# OSSI-1_Beacon_3.net
KiCad netlist of a schematic drawn in Altium Designer
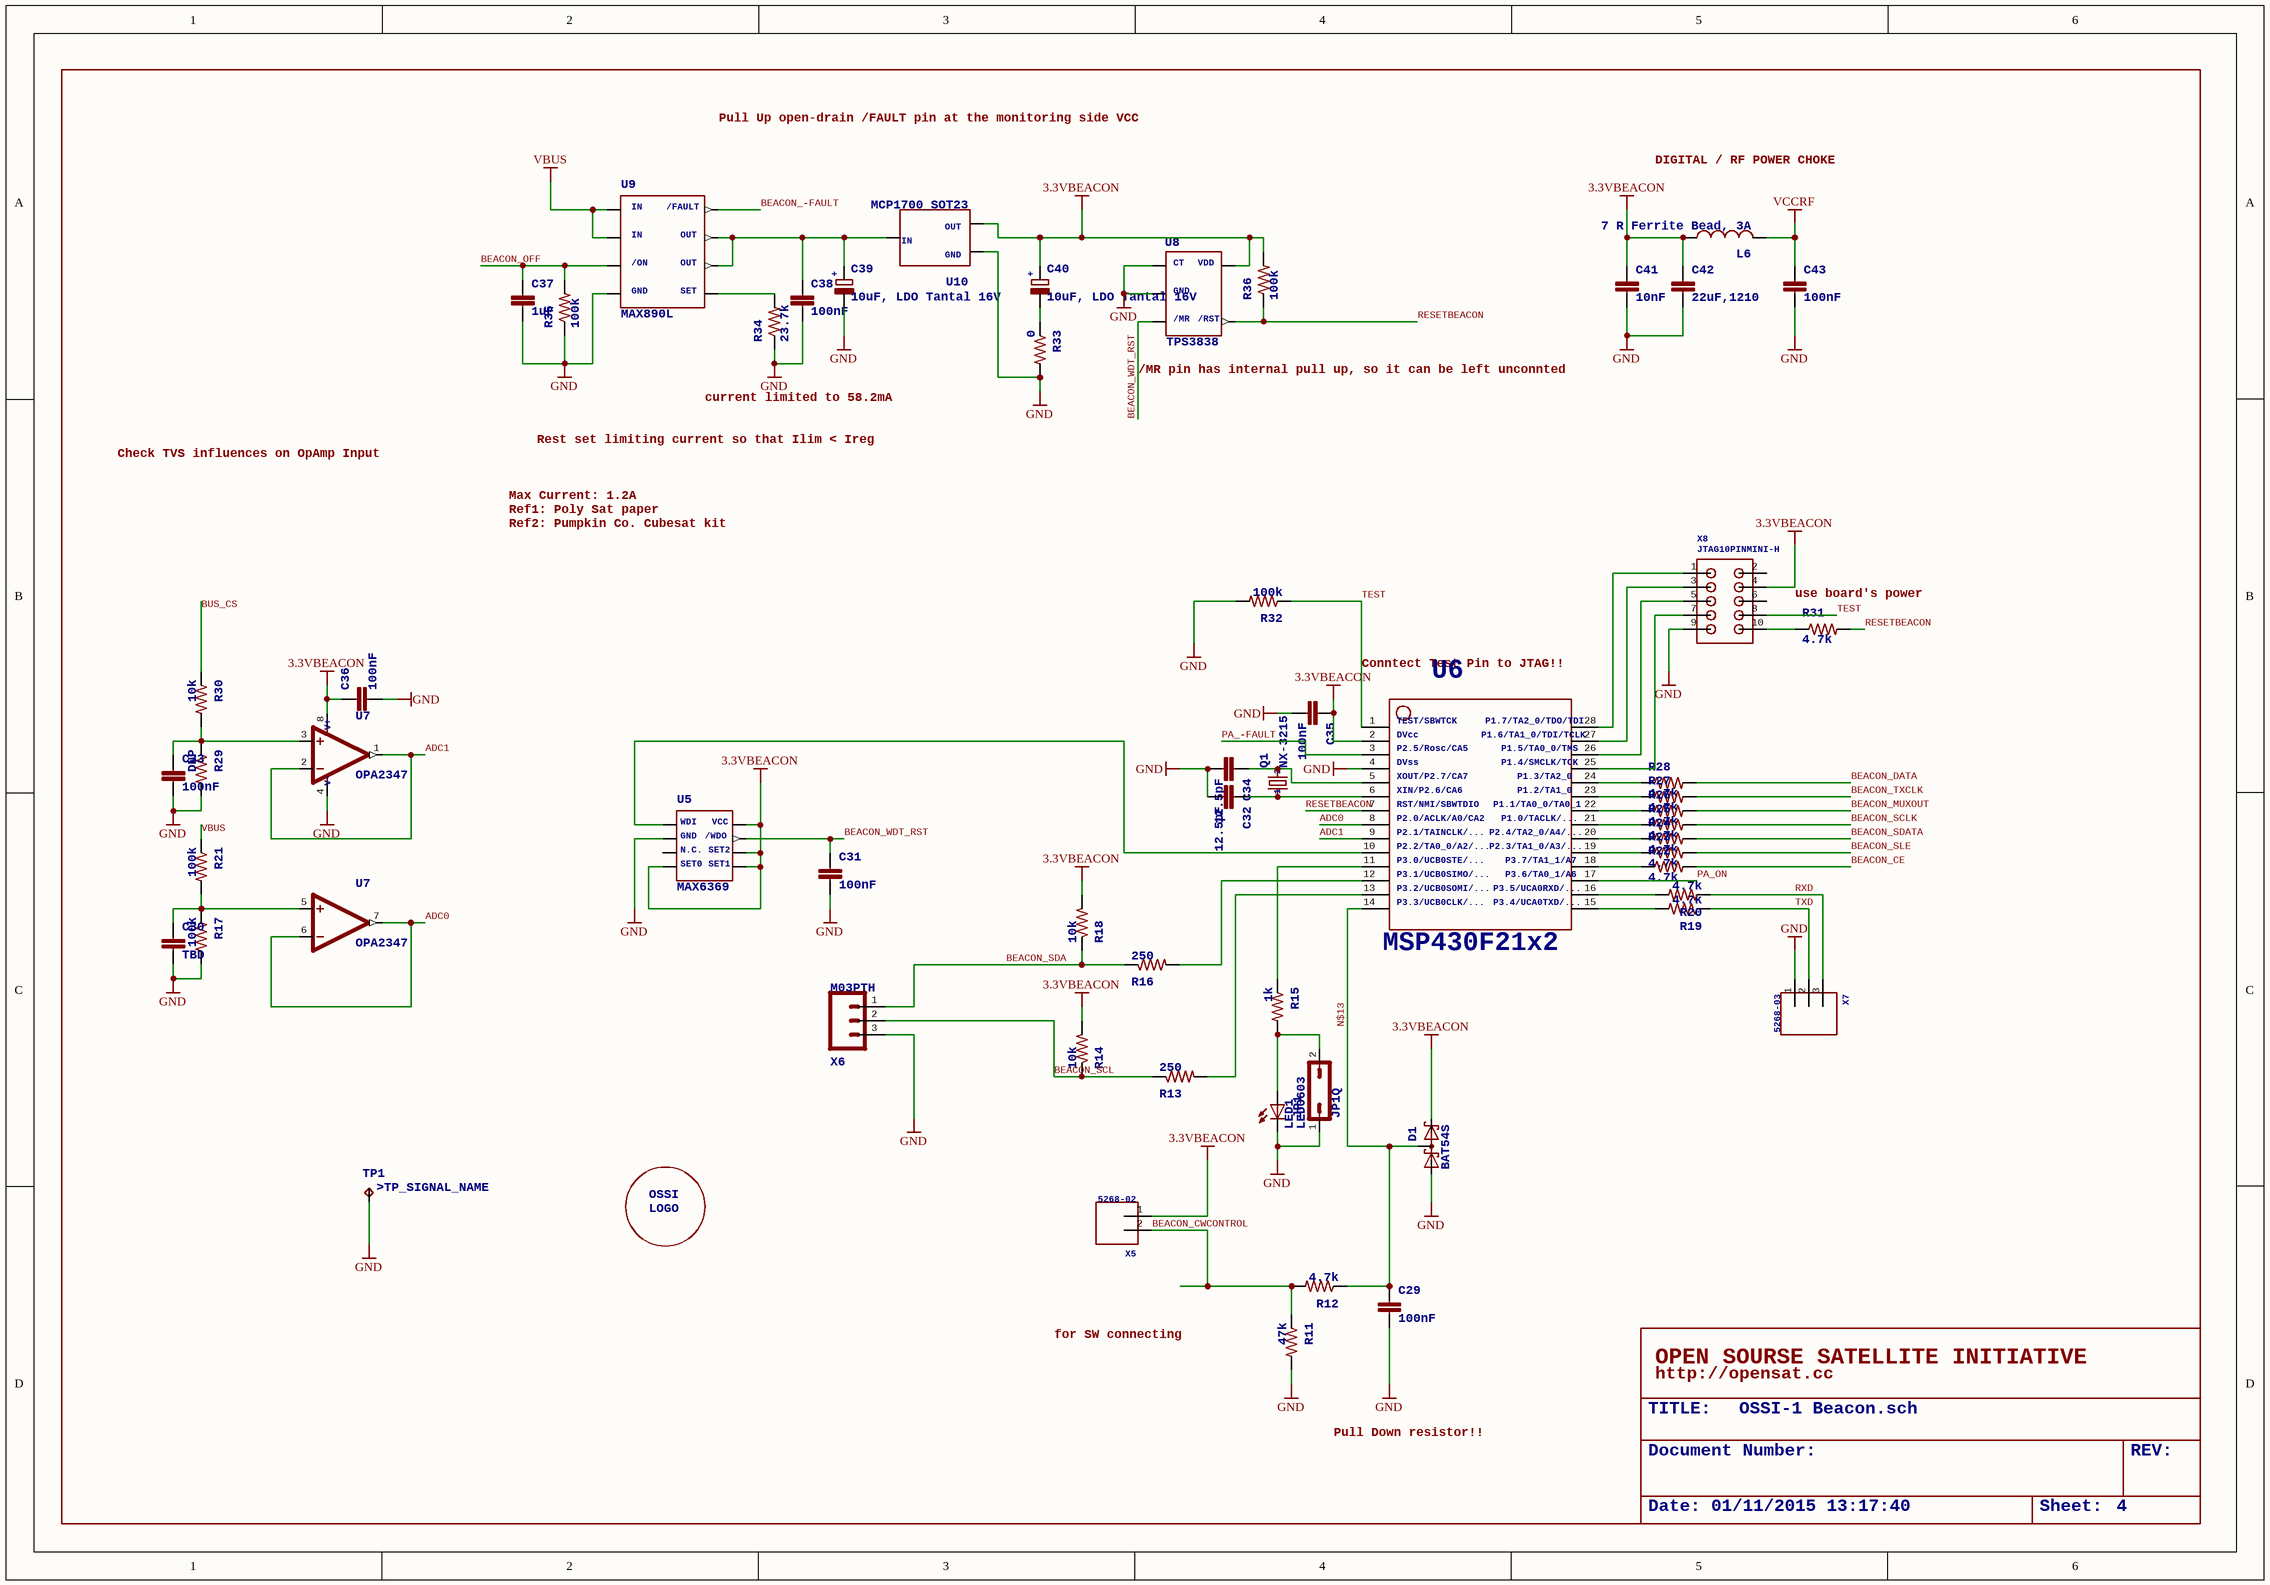
[diagram p0: OSSI-1 Beacon_3.SchDoc]

(export (version "E")
  (design (tool "Eeschema 10.0.6"))
  (components
    (comp (ref "C29")
      (value "100nF")
      (footprint "C0603(1608)")
      (fields (field (name ">NAME") "C29") (field (name ">VALUE") "100nF"))
      (libsource (lib "OSSI") (part "C0603(1608)"))
    )
    (comp (ref "C30")
      (value "TBD")
      (footprint "C0603(1608)")
      (fields (field (name ">NAME") "C30") (field (name ">VALUE") "TBD"))
      (libsource (lib "OSSI") (part "C0603(1608)"))
    )
    (comp (ref "C31")
      (value "100nF")
      (footprint "C0603(1608)")
      (fields (field (name ">NAME") "C31") (field (name ">VALUE") "100nF"))
      (libsource (lib "OSSI") (part "C0603(1608)"))
    )
    (comp (ref "C32")
      (value "12.5pF")
      (footprint "C0603(1608)")
      (fields (field (name ">NAME") "C32") (field (name ">VALUE") "12.5pF"))
      (libsource (lib "") (part "C0603(1608)_1"))
    )
    (comp (ref "C33")
      (value "100nF")
      (footprint "C0603(1608)")
      (fields (field (name ">NAME") "C33") (field (name ">VALUE") "100nF"))
      (libsource (lib "OSSI") (part "C0603(1608)"))
    )
    (comp (ref "C34")
      (value "12.5pF")
      (footprint "C0603(1608)")
      (fields (field (name ">NAME") "C34") (field (name ">VALUE") "12.5pF"))
      (libsource (lib "") (part "C0603(1608)_1"))
    )
    (comp (ref "C35")
      (value "100nF")
      (footprint "C0603(1608)")
      (fields (field (name ">NAME") "C35") (field (name ">VALUE") "100nF"))
      (libsource (lib "") (part "C0603(1608)_1"))
    )
    (comp (ref "C36")
      (value "100nF")
      (footprint "C0603(1608)")
      (fields (field (name ">NAME") "C36") (field (name ">VALUE") "100nF"))
      (libsource (lib "") (part "C0603(1608)_2"))
    )
    (comp (ref "C37")
      (value "1uF")
      (footprint "C0603(1608)")
      (fields (field (name ">NAME") "C37") (field (name ">VALUE") "1uF"))
      (libsource (lib "OSSI") (part "C0603(1608)"))
    )
    (comp (ref "C38")
      (value "100nF")
      (footprint "C0603(1608)")
      (fields (field (name ">NAME") "C38") (field (name ">VALUE") "100nF"))
      (libsource (lib "OSSI") (part "C0603(1608)"))
    )
    (comp (ref "C39")
      (value "10uF, LDO Tantal 16V")
      (footprint "C1206(3216)-A")
      (fields
        (field (name ">NAME") "C39")
        (field (name "+") "+")
        (field (name ">VALUE") "10uF, LDO Tantal 16V")
      )
      (libsource (lib "OSSI") (part "C-TANTAL-A"))
    )
    (comp (ref "C40")
      (value "10uF, LDO Tantal 16V")
      (footprint "C1206(3216)-A")
      (fields
        (field (name ">NAME") "C40")
        (field (name "+") "+")
        (field (name ">VALUE") "10uF, LDO Tantal 16V")
      )
      (libsource (lib "OSSI") (part "C-TANTAL-A"))
    )
    (comp (ref "C41")
      (value "10nF")
      (footprint "C0603(1608)")
      (fields (field (name ">NAME") "C41") (field (name ">VALUE") "10nF"))
      (libsource (lib "OSSI") (part "C0603(1608)"))
    )
    (comp (ref "C42")
      (value "22uF,1210")
      (footprint "C1210-GCM32")
      (fields (field (name ">NAME") "C42") (field (name ">VALUE") "22uF,1210"))
      (libsource (lib "OSSI") (part "C1210(3225)-GCM32"))
    )
    (comp (ref "C43")
      (value "100nF")
      (footprint "C0603(1608)")
      (fields (field (name ">NAME") "C43") (field (name ">VALUE") "100nF"))
      (libsource (lib "OSSI") (part "C0603(1608)"))
    )
    (comp (ref "D1")
      (value "BAT54S")
      (footprint "SOT23")
      (description "<b>Schottky Diodes</b><p>\nPin connection corrected 2011-05-04<br>\nSource: Fairchild .. BAT54.pdf")
      (fields (field (name ">NAME") "D1") (field (name ">VALUE") "BAT54S"))
      (libsource (lib "OSSI") (part "BAT54S"))
    )
    (comp (ref "JP1")
      (value "JP1Q")
      (footprint "JP1")
      (description "<b>JUMPER</b>")
      (fields (field (name ">NAME") "JP1") (field (name ">VALUE") "JP1Q"))
      (libsource (lib "OSSI") (part "JP1Q"))
    )
    (comp (ref "L6")
      (value "7 R Ferrite Bead, 3A")
      (footprint "L0805(2012)")
      (fields (field (name ">NAME") "L6") (field (name ">VALUE") "7 R Ferrite Bead, 3A"))
      (libsource (lib "OSSI") (part "L0805(2012)"))
    )
    (comp (ref "LED1")
      (value "LED0603")
      (footprint "LED-0603")
      (fields (field (name ">NAME") "LED1") (field (name ">VALUE") "LED0603"))
      (libsource (lib "SparkFun") (part "LED0603"))
    )
    (comp (ref "Q1")
      (value "NX-3215")
      (footprint "NX-3215")
      (fields
        (field (name ">NAME") "Q1")
        (field (name ">VALUE") "NX-3215")
        (field (name "1") "1")
        (field (name "2") "2")
      )
      (libsource (lib "OSSI") (part "NX-3215"))
    )
    (comp (ref "R11")
      (value "47k")
      (footprint "R0603(1608)")
      (fields (field (name ">NAME") "R11") (field (name ">VALUE") "47k"))
      (libsource (lib "OSSI") (part "R0603(1608)"))
    )
    (comp (ref "R12")
      (value "4.7k")
      (footprint "R0603(1608)")
      (fields (field (name ">NAME") "R12") (field (name ">VALUE") "4.7k"))
      (libsource (lib "OSSI") (part "R0603(1608)"))
    )
    (comp (ref "R13")
      (value "250")
      (footprint "R0603(1608)")
      (fields (field (name ">NAME") "R13") (field (name ">VALUE") "250"))
      (libsource (lib "OSSI") (part "R0603(1608)"))
    )
    (comp (ref "R14")
      (value "10k")
      (footprint "R0603(1608)")
      (fields (field (name ">NAME") "R14") (field (name ">VALUE") "10k"))
      (libsource (lib "OSSI") (part "R0603(1608)"))
    )
    (comp (ref "R15")
      (value "1k")
      (footprint "R0603(1608)")
      (fields (field (name ">NAME") "R15") (field (name ">VALUE") "1k"))
      (libsource (lib "OSSI") (part "R0603(1608)"))
    )
    (comp (ref "R16")
      (value "250")
      (footprint "R0603(1608)")
      (fields (field (name ">NAME") "R16") (field (name ">VALUE") "250"))
      (libsource (lib "OSSI") (part "R0603(1608)"))
    )
    (comp (ref "R17")
      (value "100k")
      (footprint "R0603(1608)")
      (fields (field (name ">NAME") "R17") (field (name ">VALUE") "100k"))
      (libsource (lib "OSSI") (part "R0603(1608)"))
    )
    (comp (ref "R18")
      (value "10k")
      (footprint "R0603(1608)")
      (fields (field (name ">NAME") "R18") (field (name ">VALUE") "10k"))
      (libsource (lib "OSSI") (part "R0603(1608)"))
    )
    (comp (ref "R19")
      (value "4.7k")
      (footprint "R0603(1608)")
      (fields (field (name ">NAME") "R19") (field (name ">VALUE") "4.7k"))
      (libsource (lib "OSSI") (part "R0603(1608)"))
    )
    (comp (ref "R20")
      (value "4.7k")
      (footprint "R0603(1608)")
      (fields (field (name ">NAME") "R20") (field (name ">VALUE") "4.7k"))
      (libsource (lib "OSSI") (part "R0603(1608)"))
    )
    (comp (ref "R21")
      (value "100k")
      (footprint "R0603(1608)")
      (fields (field (name ">NAME") "R21") (field (name ">VALUE") "100k"))
      (libsource (lib "OSSI") (part "R0603(1608)"))
    )
    (comp (ref "R22")
      (value "4.7k")
      (footprint "R0603(1608)")
      (fields (field (name ">NAME") "R22") (field (name ">VALUE") "4.7k"))
      (libsource (lib "OSSI") (part "R0603(1608)"))
    )
    (comp (ref "R23")
      (value "4.7k")
      (footprint "R0603(1608)")
      (fields (field (name ">NAME") "R23") (field (name ">VALUE") "4.7k"))
      (libsource (lib "OSSI") (part "R0603(1608)"))
    )
    (comp (ref "R24")
      (value "4.7k")
      (footprint "R0603(1608)")
      (fields (field (name ">NAME") "R24") (field (name ">VALUE") "4.7k"))
      (libsource (lib "OSSI") (part "R0603(1608)"))
    )
    (comp (ref "R25")
      (value "4.7k")
      (footprint "R0603(1608)")
      (fields (field (name ">NAME") "R25") (field (name ">VALUE") "4.7k"))
      (libsource (lib "OSSI") (part "R0603(1608)"))
    )
    (comp (ref "R26")
      (value "4.7k")
      (footprint "R0603(1608)")
      (fields (field (name ">NAME") "R26") (field (name ">VALUE") "4.7k"))
      (libsource (lib "OSSI") (part "R0603(1608)"))
    )
    (comp (ref "R27")
      (value "4.7k")
      (footprint "R0603(1608)")
      (fields (field (name ">NAME") "R27") (field (name ">VALUE") "4.7k"))
      (libsource (lib "OSSI") (part "R0603(1608)"))
    )
    (comp (ref "R28")
      (value "4.7k")
      (footprint "R0603(1608)")
      (fields (field (name ">NAME") "R28") (field (name ">VALUE") "4.7k"))
      (libsource (lib "OSSI") (part "R0603(1608)"))
    )
    (comp (ref "R29")
      (value "DNP")
      (footprint "R0603(1608)")
      (fields (field (name ">NAME") "R29") (field (name ">VALUE") "DNP"))
      (libsource (lib "OSSI") (part "R0603(1608)"))
    )
    (comp (ref "R30")
      (value "10k")
      (footprint "R0603(1608)")
      (fields (field (name ">NAME") "R30") (field (name ">VALUE") "10k"))
      (libsource (lib "OSSI") (part "R0603(1608)"))
    )
    (comp (ref "R31")
      (value "4.7k")
      (footprint "R0603(1608)")
      (fields (field (name ">NAME") "R31") (field (name ">VALUE") "4.7k"))
      (libsource (lib "OSSI") (part "R0603(1608)"))
    )
    (comp (ref "R32")
      (value "100k")
      (footprint "R0603(1608)")
      (fields (field (name ">NAME") "R32") (field (name ">VALUE") "100k"))
      (libsource (lib "OSSI") (part "R0603(1608)"))
    )
    (comp (ref "R33")
      (value "0")
      (footprint "R0603(1608)")
      (fields (field (name ">NAME") "R33") (field (name ">VALUE") "0"))
      (libsource (lib "OSSI") (part "R0603(1608)"))
    )
    (comp (ref "R34")
      (value "23.7k")
      (footprint "R0603(1608)")
      (fields (field (name ">NAME") "R34") (field (name ">VALUE") "23.7k"))
      (libsource (lib "OSSI") (part "R0603(1608)"))
    )
    (comp (ref "R35")
      (value "100k")
      (footprint "R0603(1608)")
      (fields (field (name ">NAME") "R35") (field (name ">VALUE") "100k"))
      (libsource (lib "OSSI") (part "R0603(1608)"))
    )
    (comp (ref "R36")
      (value "100k")
      (footprint "R0603(1608)")
      (fields (field (name ">NAME") "R36") (field (name ">VALUE") "100k"))
      (libsource (lib "OSSI") (part "R0603(1608)"))
    )
    (comp (ref "TP1")
      (value "TP")
      (footprint "TP-13")
      (fields (field (name ">NAME") "TP1") (field (name ">TP_SIGNAL_NAME") ">TP_SIGNAL_NAME"))
      (libsource (lib "OSSI") (part "TP"))
    )
    (comp (ref "U$1")
      (value "OSSILOGORECT")
      (footprint "OSSILOGORECT1005")
      (fields (field (name "OSSI") "OSSI") (field (name "LOGO") "LOGO"))
      (libsource (lib "OSSI") (part "OSSILOGORECT"))
    )
    (comp (ref "U5")
      (value "MAX6369")
      (footprint "SOT23-8")
      (fields
        (field (name "WDI") "WDI")
        (field (name "GND") "GND")
        (field (name "N.C.") "N.C.")
        (field (name "SET0") "SET0")
        (field (name "SET1") "SET1")
        (field (name "SET2") "SET2")
        (field (name "/WDO") "/WDO")
        (field (name "VCC") "VCC")
        (field (name ">NAME") "U5")
        (field (name ">VALUE") "MAX6369")
      )
      (libsource (lib "OSSI") (part "MAX6369"))
    )
    (comp (ref "U6")
      (value "MSP430F2132")
      (footprint "PW28")
      (description "*** MSP430F21x2 *** PW28")
      (fields
        (field (name "TEST/SBWTCK") "TEST/SBWTCK")
        (field (name "DVCC") "DVcc")
        (field (name "P2.5/ROSC/CA5") "P2.5/Rosc/CA5")
        (field (name "DVSS") "DVss")
        (field (name "XOUT/P2.7/CA7") "XOUT/P2.7/CA7")
        (field (name "XIN/P2.6/CA6") "XIN/P2.6/CA6")
        (field (name "RST/NMI/SBWTDIO") "RST/NMI/SBWTDIO")
        (field (name "P2.0/ACLK/A0/CA2") "P2.0/ACLK/A0/CA2")
        (field (name "P2.1/TAINCLK/...") "P2.1/TAINCLK/...")
        (field (name "P2.2/TA0_0/A2/...") "P2.2/TA0_0/A2/...")
        (field (name "P1.7/TA2_0/TDO/TDI") "P1.7/TA2_0/TDO/TDI")
        (field (name "P1.6/TA1_0/TDI/TCLK") "P1.6/TA1_0/TDI/TCLK")
        (field (name "P1.5/TA0_0/TMS") "P1.5/TA0_0/TMS")
        (field (name "P1.4/SMCLK/TCK") "P1.4/SMCLK/TCK")
        (field (name "P1.3/TA2_0") "P1.3/TA2_0")
        (field (name "P1.2/TA1_0") "P1.2/TA1_0")
        (field (name "P1.1/TA0_0/TA0_1") "P1.1/TA0_0/TA0_1")
        (field (name "P1.0/TACLK/...") "P1.0/TACLK/...")
        (field (name "P2.4/TA2_0/A4/...") "P2.4/TA2_0/A4/...")
        (field (name "P2.3/TA1_0/A3/...") "P2.3/TA1_0/A3/...")
        (field (name ">NAME") "U6")
        (field (name "MSP430F21X2") "MSP430F21x2")
        (field (name "P3.7/TA1_1/A7") "P3.7/TA1_1/A7")
        (field (name "P3.6/TA0_1/A6") "P3.6/TA0_1/A6")
        (field (name "P3.5/UCA0RXD/...") "P3.5/UCA0RXD/...")
        (field (name "P3.4/UCA0TXD/...") "P3.4/UCA0TXD/...")
        (field (name "P3.3/UCB0CLK/...") "P3.3/UCB0CLK/...")
        (field (name "P3.2/UCB0SOMI/...") "P3.2/UCB0SOMI/...")
        (field (name "P3.1/UCB0SIMO/...") "P3.1/UCB0SIMO/...")
        (field (name "P3.0/UCB0STE/...") "P3.0/UCB0STE/...")
      )
      (libsource (lib "OSSI") (part "MSP430F2132"))
    )
    (comp (ref "U7")
      (value "OPA2347")
      (footprint "SOT23-8DCN")
      (fields
        (field (name ">NAME") "U7")
        (field (name ">VALUE") "OPA2347")
        (field (name "V+") "V+")
        (field (name "V-") "V-")
      )
      (libsource (lib "OSSI") (part "OPA2347"))
    )
    (comp (ref "U8")
      (value "TPS3838")
      (footprint "SOT23-5DBV")
      (fields
        (field (name ">NAME") "U8")
        (field (name ">VALUE") "TPS3838")
        (field (name "CT") "CT")
        (field (name "/MR") "/MR")
        (field (name "GND") "GND")
        (field (name "VDD") "VDD")
        (field (name "/RST") "/RST")
      )
      (libsource (lib "OSSI") (part "TPS3838"))
    )
    (comp (ref "U9")
      (value "MAX890L")
      (footprint "SO8")
      (fields
        (field (name "IN") "IN")
        (field (name "IN_1") "IN")
        (field (name "/ON") "/ON")
        (field (name "GND") "GND")
        (field (name "SET") "SET")
        (field (name "OUT") "OUT")
        (field (name "OUT_1") "OUT")
        (field (name "/FAULT") "/FAULT")
        (field (name ">NAME") "U9")
        (field (name ">VALUE") "MAX890L")
      )
      (libsource (lib "OSSI") (part "MAX890L"))
    )
    (comp (ref "U10")
      (value "MCP1700_SOT23")
      (footprint "SOT23")
      (description "MCP1700 LDO from Microchips")
      (fields
        (field (name ">NAME") "U10")
        (field (name ">VALUE") "MCP1700_SOT23")
        (field (name "IN") "IN")
        (field (name "GND") "GND")
        (field (name "OUT") "OUT")
      )
      (libsource (lib "OSSI") (part "MCP1700_SOT23"))
    )
    (comp (ref "X5")
      (value "5268-02")
      (footprint "5628-02")
      (fields (field (name ">NAME") "X5") (field (name ">VALUE") "5268-02"))
      (libsource (lib "OSSI") (part "5268-02"))
    )
    (comp (ref "X6")
      (value "M03PTH")
      (footprint "1X03")
      (fields (field (name ">VALUE") "M03PTH") (field (name ">NAME") "X6"))
      (libsource (lib "OSSI") (part "M03PTH"))
    )
    (comp (ref "X7")
      (value "5268-03")
      (footprint "5268-03")
      (fields (field (name ">NAME") "X7") (field (name ">VALUE") "5268-03"))
      (libsource (lib "OSSI") (part "5268-03"))
    )
    (comp (ref "X8")
      (value "JTAG10PINMINI-H")
      (footprint "M50-3200545")
      (fields (field (name ">NAME") "X8") (field (name ">VALUE") "JTAG10PINMINI-H"))
      (libsource (lib "OSSI") (part "JTAG10PINMINI-H"))
    )
  )
  (nets
    (net (code "1") (name "/ADC0") (class "Default")
      (node (ref "U6") (pin "8") (pinfunction "8_8") (pintype "passive"))
      (node (ref "U7") (pin "6") (pinfunction "-IN_6") (pintype "passive"))
      (node (ref "U7") (pin "7") (pinfunction "OUT_7") (pintype "output"))
    )
    (net (code "2") (name "/ADC1") (class "Default")
      (node (ref "U6") (pin "9") (pinfunction "9_9") (pintype "passive"))
      (node (ref "U7") (pin "1") (pinfunction "OUT_1") (pintype "output"))
      (node (ref "U7") (pin "2") (pinfunction "-IN_2") (pintype "passive"))
    )
    (net (code "3") (name "/BEACON_-FAULT") (class "Default")
      (node (ref "U9") (pin "8") (pinfunction "P$8_8") (pintype "output"))
    )
    (net (code "4") (name "/BEACON_CE") (class "Default")
      (node (ref "R22") (pin "2") (pinfunction "2_2") (pintype "passive"))
    )
    (net (code "5") (name "/BEACON_CWCONTROL") (class "Default")
      (node (ref "R11") (pin "1") (pinfunction "1_1") (pintype "passive"))
      (node (ref "R12") (pin "2") (pinfunction "2_2") (pintype "passive"))
      (node (ref "X5") (pin "2") (pinfunction "2_2") (pintype "passive"))
    )
    (net (code "6") (name "/BEACON_DATA") (class "Default")
      (node (ref "R28") (pin "2") (pinfunction "2_2") (pintype "passive"))
    )
    (net (code "7") (name "/BEACON_MUXOUT") (class "Default")
      (node (ref "R26") (pin "2") (pinfunction "2_2") (pintype "passive"))
    )
    (net (code "8") (name "/BEACON_OFF") (class "Default")
      (node (ref "C37") (pin "1") (pinfunction "1_1") (pintype "passive"))
      (node (ref "R35") (pin "2") (pinfunction "2_2") (pintype "passive"))
      (node (ref "U9") (pin "3") (pinfunction "P$3_3") (pintype "passive"))
    )
    (net (code "9") (name "/BEACON_SCL") (class "Default")
      (node (ref "R13") (pin "1") (pinfunction "1_1") (pintype "passive"))
      (node (ref "R14") (pin "1") (pinfunction "1_1") (pintype "passive"))
      (node (ref "X6") (pin "2") (pinfunction "2_2") (pintype "passive"))
    )
    (net (code "10") (name "/BEACON_SCLK") (class "Default")
      (node (ref "R25") (pin "2") (pinfunction "2_2") (pintype "passive"))
    )
    (net (code "11") (name "/BEACON_SDA") (class "Default")
      (node (ref "R16") (pin "1") (pinfunction "1_1") (pintype "passive"))
      (node (ref "R18") (pin "1") (pinfunction "1_1") (pintype "passive"))
      (node (ref "X6") (pin "1") (pinfunction "1_1") (pintype "passive"))
    )
    (net (code "12") (name "/BEACON_SDATA") (class "Default")
      (node (ref "R24") (pin "2") (pinfunction "2_2") (pintype "passive"))
    )
    (net (code "13") (name "/BEACON_SLE") (class "Default")
      (node (ref "R23") (pin "2") (pinfunction "2_2") (pintype "passive"))
    )
    (net (code "14") (name "/BEACON_TXCLK") (class "Default")
      (node (ref "R27") (pin "2") (pinfunction "2_2") (pintype "passive"))
    )
    (net (code "15") (name "/BEACON_WDT_RST") (class "Default")
      (node (ref "C31") (pin "1") (pinfunction "1_1") (pintype "passive"))
      (node (ref "U5") (pin "7") (pinfunction "P$7_7") (pintype "output"))
      (node (ref "U8") (pin "3") (pinfunction "P$3_3") (pintype "passive"))
    )
    (net (code "16") (name "/BUS_CS") (class "Default")
      (node (ref "R30") (pin "1") (pinfunction "1_1") (pintype "passive"))
    )
    (net (code "17") (name "/N$13") (class "Default")
      (node (ref "C29") (pin "1") (pinfunction "1_1") (pintype "passive"))
      (node (ref "D1") (pin "3") (pinfunction "C1A2_3") (pintype "passive"))
      (node (ref "R12") (pin "1") (pinfunction "1_1") (pintype "passive"))
      (node (ref "U6") (pin "14") (pinfunction "14_14") (pintype "passive"))
    )
    (net (code "18") (name "/PA_-FAULT") (class "Default")
      (node (ref "U6") (pin "3") (pinfunction "3_3") (pintype "passive"))
    )
    (net (code "19") (name "/PA_ON") (class "Default")
      (node (ref "U6") (pin "17") (pinfunction "17_17") (pintype "passive"))
    )
    (net (code "20") (name "/RESETBEACON") (class "Default")
      (node (ref "R31") (pin "2") (pinfunction "2_2") (pintype "passive"))
      (node (ref "R36") (pin "1") (pinfunction "1_1") (pintype "passive"))
      (node (ref "U6") (pin "7") (pinfunction "7_7") (pintype "passive"))
      (node (ref "U8") (pin "4") (pinfunction "P$4_4") (pintype "output"))
    )
    (net (code "21") (name "/RXD") (class "Default")
      (node (ref "R20") (pin "1") (pinfunction "1_1") (pintype "passive"))
      (node (ref "X7") (pin "3") (pinfunction "3_3") (pintype "passive"))
    )
    (net (code "22") (name "/TEST") (class "Default")
      (node (ref "R32") (pin "1") (pinfunction "1_1") (pintype "passive"))
      (node (ref "U6") (pin "1") (pinfunction "1_1") (pintype "passive"))
      (node (ref "X8") (pin "8") (pinfunction "8_8") (pintype "passive"))
    )
    (net (code "23") (name "/TXD") (class "Default")
      (node (ref "R19") (pin "1") (pinfunction "1_1") (pintype "passive"))
      (node (ref "X7") (pin "2") (pinfunction "2_2") (pintype "passive"))
    )
    (net (code "24") (name "3.3VBEACON") (class "Default")
      (node (ref "C35") (pin "1") (pinfunction "1_1") (pintype "passive"))
      (node (ref "C36") (pin "1") (pinfunction "1_1") (pintype "passive"))
      (node (ref "C40") (pin "1") (pinfunction "+_1") (pintype "passive"))
      (node (ref "C41") (pin "1") (pinfunction "1_1") (pintype "passive"))
      (node (ref "C42") (pin "P$1") (pinfunction "1_P$1") (pintype "passive"))
      (node (ref "D1") (pin "2") (pinfunction "C2_2") (pintype "passive"))
      (node (ref "L6") (pin "1") (pinfunction "1_1") (pintype "passive"))
      (node (ref "R14") (pin "2") (pinfunction "2_2") (pintype "passive"))
      (node (ref "R18") (pin "2") (pinfunction "2_2") (pintype "passive"))
      (node (ref "R36") (pin "2") (pinfunction "2_2") (pintype "passive"))
      (node (ref "U10") (pin "2") (pinfunction "2_2") (pintype "power_in"))
      (node (ref "U5") (pin "4") (pinfunction "P$4_4") (pintype "passive"))
      (node (ref "U5") (pin "5") (pinfunction "P$5_5") (pintype "passive"))
      (node (ref "U5") (pin "6") (pinfunction "P$6_6") (pintype "passive"))
      (node (ref "U5") (pin "8") (pinfunction "P$8_8") (pintype "power_in"))
      (node (ref "U6") (pin "2") (pinfunction "2_2") (pintype "power_in"))
      (node (ref "U7") (pin "8") (pinfunction "V+_8") (pintype "power_in"))
      (node (ref "U8") (pin "5") (pinfunction "P$5_5") (pintype "power_in"))
      (node (ref "X5") (pin "1") (pinfunction "1_1") (pintype "passive"))
      (node (ref "X8") (pin "4") (pinfunction "4_4") (pintype "passive"))
    )
    (net (code "25") (name "GND") (class "Default")
      (node (ref "C29") (pin "2") (pinfunction "2_2") (pintype "passive"))
      (node (ref "C30") (pin "2") (pinfunction "2_2") (pintype "passive"))
      (node (ref "C31") (pin "2") (pinfunction "2_2") (pintype "passive"))
      (node (ref "C32") (pin "2") (pinfunction "2_2") (pintype "passive"))
      (node (ref "C33") (pin "2") (pinfunction "2_2") (pintype "passive"))
      (node (ref "C34") (pin "2") (pinfunction "2_2") (pintype "passive"))
      (node (ref "C35") (pin "2") (pinfunction "2_2") (pintype "passive"))
      (node (ref "C36") (pin "2") (pinfunction "2_2") (pintype "passive"))
      (node (ref "C37") (pin "2") (pinfunction "2_2") (pintype "passive"))
      (node (ref "C38") (pin "2") (pinfunction "2_2") (pintype "passive"))
      (node (ref "C39") (pin "2") (pinfunction "-_2") (pintype "passive"))
      (node (ref "C41") (pin "2") (pinfunction "2_2") (pintype "passive"))
      (node (ref "C42") (pin "P$2") (pinfunction "2_P$2") (pintype "passive"))
      (node (ref "C43") (pin "2") (pinfunction "2_2") (pintype "passive"))
      (node (ref "D1") (pin "1") (pinfunction "A1_1") (pintype "passive"))
      (node (ref "JP1") (pin "1") (pinfunction "1_1") (pintype "passive"))
      (node (ref "LED1") (pin "C") (pinfunction "C_C") (pintype "passive"))
      (node (ref "R11") (pin "2") (pinfunction "2_2") (pintype "passive"))
      (node (ref "R17") (pin "2") (pinfunction "2_2") (pintype "passive"))
      (node (ref "R29") (pin "2") (pinfunction "2_2") (pintype "passive"))
      (node (ref "R32") (pin "2") (pinfunction "2_2") (pintype "passive"))
      (node (ref "R33") (pin "2") (pinfunction "2_2") (pintype "passive"))
      (node (ref "R34") (pin "1") (pinfunction "1_1") (pintype "passive"))
      (node (ref "R35") (pin "1") (pinfunction "1_1") (pintype "passive"))
      (node (ref "TP1") (pin "TP") (pinfunction "TP_TP") (pintype "passive"))
      (node (ref "U10") (pin "1") (pinfunction "1_1") (pintype "power_in"))
      (node (ref "U5") (pin "2") (pinfunction "P$2_2") (pintype "power_in"))
      (node (ref "U6") (pin "4") (pinfunction "4_4") (pintype "power_in"))
      (node (ref "U7") (pin "4") (pinfunction "V-_4") (pintype "power_in"))
      (node (ref "U8") (pin "1") (pinfunction "P$1_1") (pintype "passive"))
      (node (ref "U8") (pin "2") (pinfunction "P$2_2") (pintype "power_in"))
      (node (ref "U9") (pin "4") (pinfunction "P$4_4") (pintype "power_in"))
      (node (ref "X6") (pin "3") (pinfunction "3_3") (pintype "passive"))
      (node (ref "X7") (pin "1") (pinfunction "1_1") (pintype "passive"))
      (node (ref "X8") (pin "9") (pinfunction "9_9") (pintype "passive"))
    )
    (net (code "26") (name "Net-(C32-Pad1)") (class "Default")
      (node (ref "C32") (pin "1") (pinfunction "1_1") (pintype "passive"))
      (node (ref "Q1") (pin "1") (pinfunction "1_1") (pintype "passive"))
      (node (ref "U6") (pin "6") (pinfunction "6_6") (pintype "passive"))
    )
    (net (code "27") (name "Net-(C34-Pad1)") (class "Default")
      (node (ref "C34") (pin "1") (pinfunction "1_1") (pintype "passive"))
      (node (ref "Q1") (pin "2") (pinfunction "2_2") (pintype "passive"))
      (node (ref "U6") (pin "5") (pinfunction "5_5") (pintype "passive"))
    )
    (net (code "28") (name "Net-(C39-+)") (class "Default")
      (node (ref "C38") (pin "1") (pinfunction "1_1") (pintype "passive"))
      (node (ref "C39") (pin "1") (pinfunction "+_1") (pintype "passive"))
      (node (ref "U10") (pin "3") (pinfunction "3_3") (pintype "power_in"))
      (node (ref "U9") (pin "6") (pinfunction "P$6_6") (pintype "output"))
      (node (ref "U9") (pin "7") (pinfunction "P$7_7") (pintype "output"))
    )
    (net (code "29") (name "Net-(C40--)") (class "Default")
      (node (ref "C40") (pin "2") (pinfunction "-_2") (pintype "passive"))
      (node (ref "R33") (pin "1") (pinfunction "1_1") (pintype "passive"))
    )
    (net (code "30") (name "Net-(JP1-Pad2)") (class "Default")
      (node (ref "JP1") (pin "2") (pinfunction "2_2") (pintype "passive"))
      (node (ref "LED1") (pin "A") (pinfunction "A_A") (pintype "passive"))
      (node (ref "R15") (pin "2") (pinfunction "2_2") (pintype "passive"))
    )
    (net (code "31") (name "Net-(R13-Pad2)") (class "Default")
      (node (ref "R13") (pin "2") (pinfunction "2_2") (pintype "passive"))
      (node (ref "U6") (pin "13") (pinfunction "13_13") (pintype "passive"))
    )
    (net (code "32") (name "Net-(R15-Pad1)") (class "Default")
      (node (ref "R15") (pin "1") (pinfunction "1_1") (pintype "passive"))
      (node (ref "U6") (pin "11") (pinfunction "11_11") (pintype "passive"))
    )
    (net (code "33") (name "Net-(R16-Pad2)") (class "Default")
      (node (ref "R16") (pin "2") (pinfunction "2_2") (pintype "passive"))
      (node (ref "U6") (pin "12") (pinfunction "12_12") (pintype "passive"))
    )
    (net (code "34") (name "Net-(R19-Pad2)") (class "Default")
      (node (ref "R19") (pin "2") (pinfunction "2_2") (pintype "passive"))
      (node (ref "U6") (pin "15") (pinfunction "15_15") (pintype "passive"))
    )
    (net (code "35") (name "Net-(R20-Pad2)") (class "Default")
      (node (ref "R20") (pin "2") (pinfunction "2_2") (pintype "passive"))
      (node (ref "U6") (pin "16") (pinfunction "16_16") (pintype "passive"))
    )
    (net (code "36") (name "Net-(R22-Pad1)") (class "Default")
      (node (ref "R22") (pin "1") (pinfunction "1_1") (pintype "passive"))
      (node (ref "U6") (pin "18") (pinfunction "18_18") (pintype "passive"))
    )
    (net (code "37") (name "Net-(R23-Pad1)") (class "Default")
      (node (ref "R23") (pin "1") (pinfunction "1_1") (pintype "passive"))
      (node (ref "U6") (pin "19") (pinfunction "19_19") (pintype "passive"))
    )
    (net (code "38") (name "Net-(R24-Pad1)") (class "Default")
      (node (ref "R24") (pin "1") (pinfunction "1_1") (pintype "passive"))
      (node (ref "U6") (pin "20") (pinfunction "20_20") (pintype "passive"))
    )
    (net (code "39") (name "Net-(R25-Pad1)") (class "Default")
      (node (ref "R25") (pin "1") (pinfunction "1_1") (pintype "passive"))
      (node (ref "U6") (pin "21") (pinfunction "21_21") (pintype "passive"))
    )
    (net (code "40") (name "Net-(R26-Pad1)") (class "Default")
      (node (ref "R26") (pin "1") (pinfunction "1_1") (pintype "passive"))
      (node (ref "U6") (pin "22") (pinfunction "22_22") (pintype "passive"))
    )
    (net (code "41") (name "Net-(R27-Pad1)") (class "Default")
      (node (ref "R27") (pin "1") (pinfunction "1_1") (pintype "passive"))
      (node (ref "U6") (pin "23") (pinfunction "23_23") (pintype "passive"))
    )
    (net (code "42") (name "Net-(R28-Pad1)") (class "Default")
      (node (ref "R28") (pin "1") (pinfunction "1_1") (pintype "passive"))
      (node (ref "U6") (pin "24") (pinfunction "24_24") (pintype "passive"))
    )
    (net (code "43") (name "Net-(R31-Pad1)") (class "Default")
      (node (ref "R31") (pin "1") (pinfunction "1_1") (pintype "passive"))
      (node (ref "X8") (pin "10") (pinfunction "10_10") (pintype "passive"))
    )
    (net (code "44") (name "Net-(U5-P$1)") (class "Default")
      (node (ref "U5") (pin "1") (pinfunction "P$1_1") (pintype "passive"))
      (node (ref "U6") (pin "10") (pinfunction "10_10") (pintype "passive"))
    )
    (net (code "45") (name "Net-(U6-Pad25)") (class "Default")
      (node (ref "U6") (pin "25") (pinfunction "25_25") (pintype "passive"))
      (node (ref "X8") (pin "7") (pinfunction "7_7") (pintype "passive"))
    )
    (net (code "46") (name "Net-(U6-Pad26)") (class "Default")
      (node (ref "U6") (pin "26") (pinfunction "26_26") (pintype "passive"))
      (node (ref "X8") (pin "5") (pinfunction "5_5") (pintype "passive"))
    )
    (net (code "47") (name "Net-(U6-Pad27)") (class "Default")
      (node (ref "U6") (pin "27") (pinfunction "27_27") (pintype "passive"))
      (node (ref "X8") (pin "3") (pinfunction "3_3") (pintype "passive"))
    )
    (net (code "48") (name "Net-(U6-Pad28)") (class "Default")
      (node (ref "U6") (pin "28") (pinfunction "28_28") (pintype "passive"))
      (node (ref "X8") (pin "1") (pinfunction "1_1") (pintype "passive"))
    )
    (net (code "49") (name "Net-(U7A-+IN)") (class "Default")
      (node (ref "C33") (pin "1") (pinfunction "1_1") (pintype "passive"))
      (node (ref "R29") (pin "1") (pinfunction "1_1") (pintype "passive"))
      (node (ref "R30") (pin "2") (pinfunction "2_2") (pintype "passive"))
      (node (ref "U7") (pin "3") (pinfunction "+IN_3") (pintype "passive"))
    )
    (net (code "50") (name "Net-(U7B-+IN)") (class "Default")
      (node (ref "C30") (pin "1") (pinfunction "1_1") (pintype "passive"))
      (node (ref "R17") (pin "1") (pinfunction "1_1") (pintype "passive"))
      (node (ref "R21") (pin "2") (pinfunction "2_2") (pintype "passive"))
      (node (ref "U7") (pin "5") (pinfunction "+IN_5") (pintype "passive"))
    )
    (net (code "51") (name "Net-(U9-P$5)") (class "Default")
      (node (ref "R34") (pin "2") (pinfunction "2_2") (pintype "passive"))
      (node (ref "U9") (pin "5") (pinfunction "P$5_5") (pintype "passive"))
    )
    (net (code "52") (name "VBUS") (class "Default")
      (node (ref "R21") (pin "1") (pinfunction "1_1") (pintype "passive"))
      (node (ref "U9") (pin "1") (pinfunction "P$1_1") (pintype "passive"))
      (node (ref "U9") (pin "2") (pinfunction "P$2_2") (pintype "passive"))
    )
    (net (code "53") (name "VCCRF") (class "Default")
      (node (ref "C43") (pin "1") (pinfunction "1_1") (pintype "passive"))
      (node (ref "L6") (pin "2") (pinfunction "2_2") (pintype "passive"))
    )
    (net (code "54") (name "unconnected-(U5-P$3-Pad3)") (class "Default")
      (node (ref "U5") (pin "3") (pinfunction "P$3_3") (pintype "passive"))
    )
    (net (code "55") (name "unconnected-(X8-Pad2)") (class "Default")
      (node (ref "X8") (pin "2") (pinfunction "2_2") (pintype "passive"))
    )
    (net (code "56") (name "unconnected-(X8-Pad6)") (class "Default")
      (node (ref "X8") (pin "6") (pinfunction "6_6") (pintype "passive"))
    )
  )
)
